# powerboard_3_3V_5V.net
KiCad netlist of a schematic drawn in EAGLE
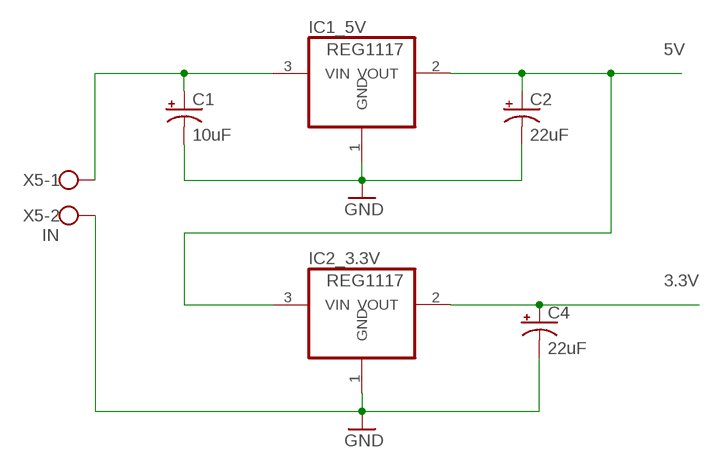
[diagram p0: schematic, sheet 1]

(export (version "E")
  (design (tool "Eeschema 10.0.6"))
  (components
    (comp (ref "C1")
      (value "10uF")
      (footprint "eagle-import:EIA3216")
      (libsource (lib "eagle-import") (part "10UF-POLAR-EIA3216-16V-10%(TANT)"))
    )
    (comp (ref "C2")
      (value "22uF")
      (footprint "eagle-import:EIA3528")
      (libsource (lib "eagle-import") (part "10UF-POLAR-EIA3528-20V-10%(TANT)"))
    )
    (comp (ref "C4")
      (value "22uF")
      (footprint "eagle-import:EIA3528")
      (libsource (lib "eagle-import") (part "10UF-POLAR-EIA3528-20V-10%(TANT)"))
    )
    (comp (ref "IC1_5V")
      (value "REG1117")
      (footprint "eagle-import:SOT223")
      (libsource (lib "eagle-import") (part "REG1117"))
    )
    (comp (ref "IC2_3.3V")
      (value "REG1117")
      (footprint "eagle-import:SOT223")
      (libsource (lib "eagle-import") (part "REG1117"))
    )
    (comp (ref "X5")
      (value "IN")
      (footprint "eagle-import:W237-102")
      (fields (field (name "MPN") "237-102"))
      (libsource (lib "eagle-import") (part "W237-102"))
    )
  )
  (nets
    (net (code "1") (name "/3.3V") (class "Default")
      (node (ref "C4") (pin "A") (pinfunction "+_A") (pintype "passive"))
      (node (ref "IC2_3.3V") (pin "2") (pinfunction "VOUT_2") (pintype "output"))
    )
    (net (code "2") (name "/5V") (class "Default")
      (node (ref "C2") (pin "A") (pinfunction "+_A") (pintype "passive"))
      (node (ref "IC1_5V") (pin "2") (pinfunction "VOUT_2") (pintype "output"))
      (node (ref "IC2_3.3V") (pin "3") (pinfunction "VIN_3") (pintype "input"))
    )
    (net (code "3") (name "GND") (class "Default")
      (node (ref "C1") (pin "-") (pinfunction "-_-") (pintype "passive"))
      (node (ref "C2") (pin "C") (pinfunction "-_C") (pintype "passive"))
      (node (ref "C4") (pin "C") (pinfunction "-_C") (pintype "passive"))
      (node (ref "IC1_5V") (pin "1") (pinfunction "GND_1") (pintype "power_in"))
      (node (ref "IC2_3.3V") (pin "1") (pinfunction "GND_1") (pintype "power_in"))
      (node (ref "X5") (pin "2") (pinfunction "KL_2") (pintype "passive"))
    )
    (net (code "4") (name "Net-(IC1_5V-VIN)") (class "Default")
      (node (ref "C1") (pin "+") (pinfunction "+_+") (pintype "passive"))
      (node (ref "IC1_5V") (pin "3") (pinfunction "VIN_3") (pintype "input"))
      (node (ref "X5") (pin "1") (pinfunction "KL_1") (pintype "passive"))
    )
  )
)
